# LED_Driver.net
KiCad netlist of a schematic drawn in Altium Designer
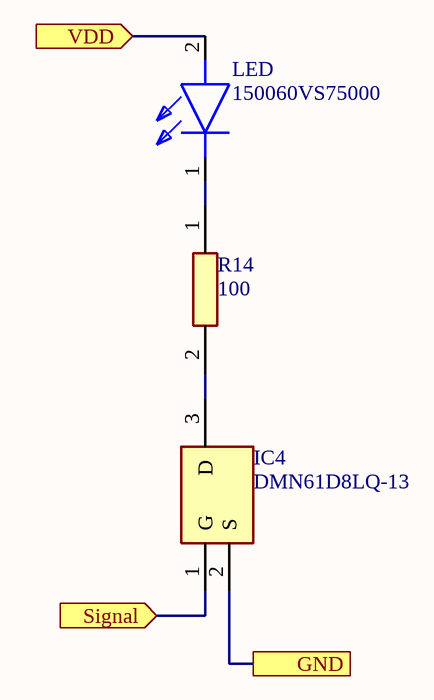
[diagram p0: LED_Driver.SchDoc]

(export (version "E")
  (design (tool "Eeschema 10.0.6"))
  (components
    (comp (ref "IC4")
      (value "DMN61D8LQ-13")
      (footprint "SamacSys:SOT96P240X110-3N")
      (description "Integrated Circuit")
      (fields (field (name "MOUSER PART NUMBER") "621-DMN61D8LQ-13"))
      (libsource (lib "SamacSys") (part "DMN61D8LQ-13"))
    )
    (comp (ref "LED")
      (value "150060VS75000")
      (footprint "SamacSys:LEDC1608X70N")
      (description "LED")
      (fields (field (name "MOUSER PART NUMBER") "710-150060VS75000"))
      (libsource (lib "*") (part "150060VS75000"))
    )
    (comp (ref "R14")
      (value "100")
      (footprint "SamacSys:RESC1608X55N")
      (description "Resistor")
      (fields
        (field (name "MANUFACTURER_PART_NUMBER") "RC0603JR-7W100RL")
        (field (name "MOUSER PART NUMBER") "603-RC0603JR-7W100RL")
      )
      (libsource (lib "*") (part "RC0603JR-7W100RL"))
    )
  )
  (nets
    (net (code "1") (name "/GND") (class "Default")
      (node (ref "IC4") (pin "2") (pinfunction "S_2") (pintype "passive"))
    )
    (net (code "2") (name "/Signal") (class "Default")
      (node (ref "IC4") (pin "1") (pinfunction "G_1") (pintype "passive"))
    )
    (net (code "3") (name "/VDD") (class "Default")
      (node (ref "LED") (pin "2") (pinfunction "A_2") (pintype "passive"))
    )
    (net (code "4") (name "Net-(IC4-D)") (class "Default")
      (node (ref "IC4") (pin "3") (pinfunction "D_3") (pintype "passive"))
      (node (ref "R14") (pin "2") (pinfunction "2_2") (pintype "passive"))
    )
    (net (code "5") (name "Net-(LED-K)") (class "Default")
      (node (ref "LED") (pin "1") (pinfunction "K_1") (pintype "passive"))
      (node (ref "R14") (pin "1") (pinfunction "1_1") (pintype "passive"))
    )
  )
)
